# spi2par2019backpack.net
KiCad netlist of a schematic drawn in EAGLE
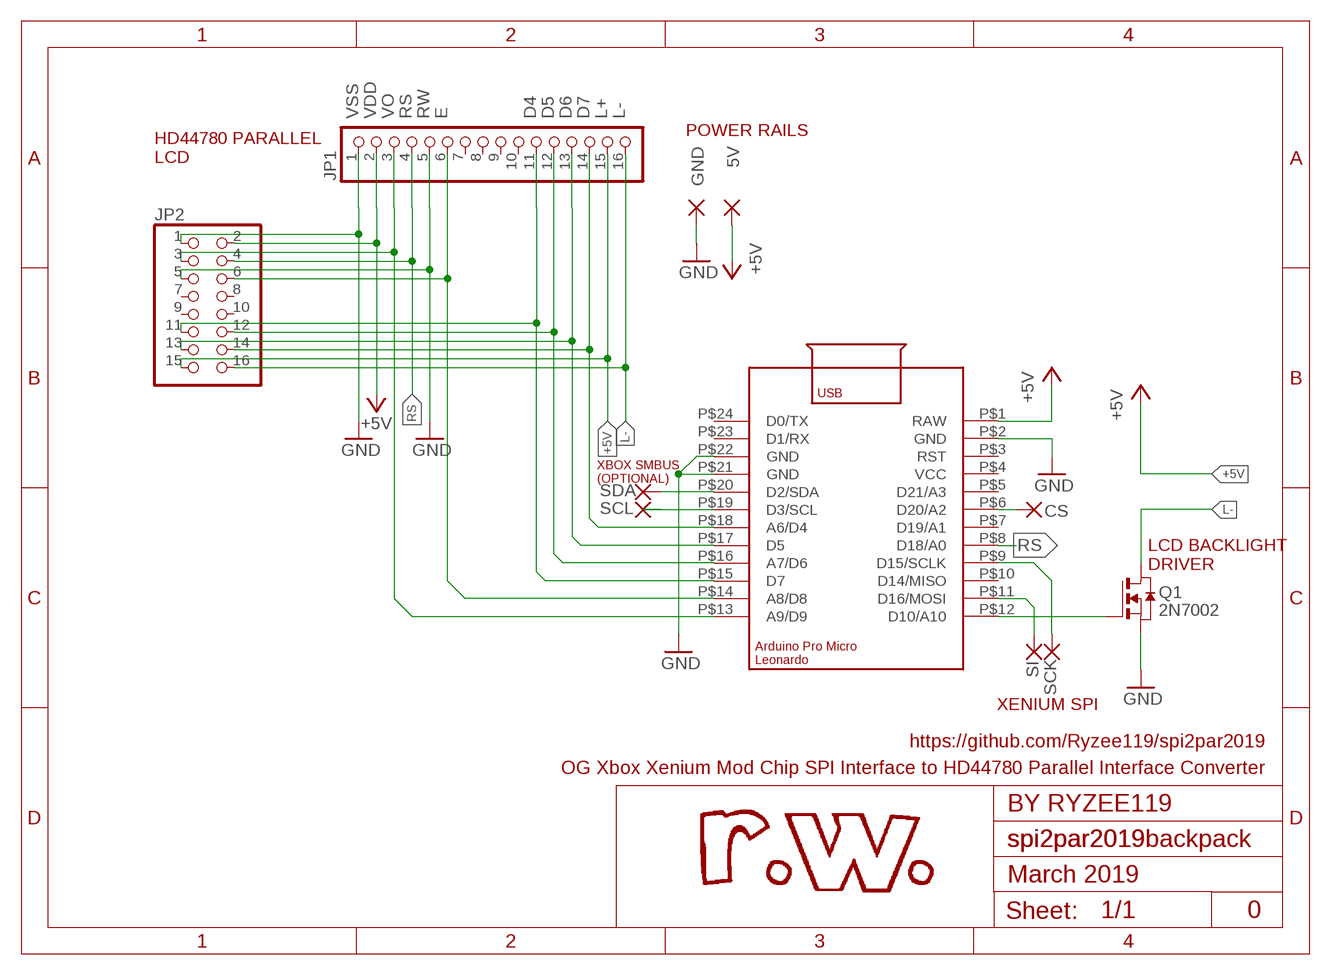
[diagram p0: schematic, sheet 1]

(export (version "E")
  (design (tool "Eeschema 10.0.6"))
  (components
    (comp (ref "5V")
      (value "WIREPADSMD1,27-254")
      (footprint "eagle-import:SMD1,27-2,54")
      (libsource (lib "eagle-import") (part "WIREPADSMD1,27-254"))
    )
    (comp (ref "CS")
      (value "WIREPADSMD1,27-254")
      (footprint "eagle-import:SMD1,27-2,54")
      (libsource (lib "eagle-import") (part "WIREPADSMD1,27-254"))
    )
    (comp (ref "GND")
      (value "WIREPADSMD1,27-254")
      (footprint "eagle-import:SMD1,27-2,54")
      (libsource (lib "eagle-import") (part "WIREPADSMD1,27-254"))
    )
    (comp (ref "JP1")
      (value "PINHD-1X16")
      (footprint "eagle-import:1X16")
      (libsource (lib "eagle-import") (part "PINHD-1X16"))
    )
    (comp (ref "JP2")
      (value "PINHD-2X8")
      (footprint "eagle-import:2X08")
      (libsource (lib "eagle-import") (part "PINHD-2X8"))
    )
    (comp (ref "Q1")
      (value "2N70026Ω")
      (footprint "eagle-import:SOT-23")
      (libsource (lib "eagle-import") (part "NMOSSOT23"))
    )
    (comp (ref "SCK")
      (value "WIREPADSMD1,27-254")
      (footprint "eagle-import:SMD1,27-2,54")
      (libsource (lib "eagle-import") (part "WIREPADSMD1,27-254"))
    )
    (comp (ref "SCL")
      (value "WIREPADSMD1,27-254")
      (footprint "eagle-import:SMD1,27-2,54")
      (libsource (lib "eagle-import") (part "WIREPADSMD1,27-254"))
    )
    (comp (ref "SDA")
      (value "WIREPADSMD1,27-254")
      (footprint "eagle-import:SMD1,27-2,54")
      (libsource (lib "eagle-import") (part "WIREPADSMD1,27-254"))
    )
    (comp (ref "SI")
      (value "WIREPADSMD1,27-254")
      (footprint "eagle-import:SMD1,27-2,54")
      (libsource (lib "eagle-import") (part "WIREPADSMD1,27-254"))
    )
    (comp (ref "U1")
      (value "ARDUINO_LEONARDO_MICRO")
      (footprint "eagle-import:ARDUINO_LEONARDO_MICRO")
      (libsource (lib "eagle-import") (part "ARDUINO_LEONARDO_MICRO"))
    )
  )
  (nets
    (net (code "1") (name "+5V") (class "Default")
      (node (ref "5V") (pin "1") (pinfunction "P_1") (pintype "passive"))
      (node (ref "JP1") (pin "15") (pinfunction "15_15") (pintype "passive"))
      (node (ref "JP1") (pin "2") (pinfunction "2_2") (pintype "passive"))
      (node (ref "JP2") (pin "15") (pinfunction "15_15") (pintype "passive"))
      (node (ref "JP2") (pin "2") (pinfunction "2_2") (pintype "passive"))
      (node (ref "U1") (pin "P$1") (pinfunction "RAW_P$1") (pintype "bidirectional"))
    )
    (net (code "2") (name "GND") (class "Default")
      (node (ref "GND") (pin "1") (pinfunction "P_1") (pintype "passive"))
      (node (ref "JP1") (pin "1") (pinfunction "1_1") (pintype "passive"))
      (node (ref "JP1") (pin "5") (pinfunction "5_5") (pintype "passive"))
      (node (ref "JP2") (pin "1") (pinfunction "1_1") (pintype "passive"))
      (node (ref "JP2") (pin "5") (pinfunction "5_5") (pintype "passive"))
      (node (ref "Q1") (pin "2") (pinfunction "S_2") (pintype "passive"))
      (node (ref "U1") (pin "P$2") (pinfunction "GND_P$2") (pintype "bidirectional"))
      (node (ref "U1") (pin "P$21") (pinfunction "GND_P$21") (pintype "bidirectional"))
      (node (ref "U1") (pin "P$22") (pinfunction "GND_P$22") (pintype "bidirectional"))
    )
    (net (code "3") (name "L-") (class "Default")
      (node (ref "JP1") (pin "16") (pinfunction "16_16") (pintype "passive"))
      (node (ref "JP2") (pin "16") (pinfunction "16_16") (pintype "passive"))
      (node (ref "Q1") (pin "1") (pinfunction "D_1") (pintype "passive"))
    )
    (net (code "4") (name "Net-(CS-P)") (class "Default")
      (node (ref "CS") (pin "1") (pinfunction "P_1") (pintype "passive"))
      (node (ref "U1") (pin "P$6") (pinfunction "D20/A2_P$6") (pintype "bidirectional"))
    )
    (net (code "5") (name "Net-(Q1-G)") (class "Default")
      (node (ref "Q1") (pin "3") (pinfunction "G_3") (pintype "passive"))
      (node (ref "U1") (pin "P$12") (pinfunction "D10/A10_P$12") (pintype "bidirectional"))
    )
    (net (code "6") (name "Net-(SCK-P)") (class "Default")
      (node (ref "SCK") (pin "1") (pinfunction "P_1") (pintype "passive"))
      (node (ref "U1") (pin "P$9") (pinfunction "D15/SCLK_P$9") (pintype "bidirectional"))
    )
    (net (code "7") (name "Net-(SCL-P)") (class "Default")
      (node (ref "SCL") (pin "1") (pinfunction "P_1") (pintype "passive"))
      (node (ref "U1") (pin "P$19") (pinfunction "D3/SCL_P$19") (pintype "bidirectional"))
    )
    (net (code "8") (name "Net-(SDA-P)") (class "Default")
      (node (ref "SDA") (pin "1") (pinfunction "P_1") (pintype "passive"))
      (node (ref "U1") (pin "P$20") (pinfunction "D2/SDA_P$20") (pintype "bidirectional"))
    )
    (net (code "9") (name "Net-(SI-P)") (class "Default")
      (node (ref "SI") (pin "1") (pinfunction "P_1") (pintype "passive"))
      (node (ref "U1") (pin "P$11") (pinfunction "D16/MOSI_P$11") (pintype "bidirectional"))
    )
    (net (code "10") (name "Net-(U1-A6{slash}D4)") (class "Default")
      (node (ref "JP1") (pin "14") (pinfunction "14_14") (pintype "passive"))
      (node (ref "JP2") (pin "14") (pinfunction "14_14") (pintype "passive"))
      (node (ref "U1") (pin "P$18") (pinfunction "A6/D4_P$18") (pintype "bidirectional"))
    )
    (net (code "11") (name "Net-(U1-A7{slash}D6)") (class "Default")
      (node (ref "JP1") (pin "12") (pinfunction "12_12") (pintype "passive"))
      (node (ref "JP2") (pin "12") (pinfunction "12_12") (pintype "passive"))
      (node (ref "U1") (pin "P$16") (pinfunction "A7/D6_P$16") (pintype "bidirectional"))
    )
    (net (code "12") (name "Net-(U1-A8{slash}D8)") (class "Default")
      (node (ref "JP1") (pin "6") (pinfunction "6_6") (pintype "passive"))
      (node (ref "JP2") (pin "6") (pinfunction "6_6") (pintype "passive"))
      (node (ref "U1") (pin "P$14") (pinfunction "A8/D8_P$14") (pintype "bidirectional"))
    )
    (net (code "13") (name "Net-(U1-A9{slash}D9)") (class "Default")
      (node (ref "JP1") (pin "3") (pinfunction "3_3") (pintype "passive"))
      (node (ref "JP2") (pin "3") (pinfunction "3_3") (pintype "passive"))
      (node (ref "U1") (pin "P$13") (pinfunction "A9/D9_P$13") (pintype "bidirectional"))
    )
    (net (code "14") (name "Net-(U1-D5)") (class "Default")
      (node (ref "JP1") (pin "13") (pinfunction "13_13") (pintype "passive"))
      (node (ref "JP2") (pin "13") (pinfunction "13_13") (pintype "passive"))
      (node (ref "U1") (pin "P$17") (pinfunction "D5_P$17") (pintype "bidirectional"))
    )
    (net (code "15") (name "Net-(U1-D7)") (class "Default")
      (node (ref "JP1") (pin "11") (pinfunction "11_11") (pintype "passive"))
      (node (ref "JP2") (pin "11") (pinfunction "11_11") (pintype "passive"))
      (node (ref "U1") (pin "P$15") (pinfunction "D7_P$15") (pintype "bidirectional"))
    )
    (net (code "16") (name "RS") (class "Default")
      (node (ref "JP1") (pin "4") (pinfunction "4_4") (pintype "passive"))
      (node (ref "JP2") (pin "4") (pinfunction "4_4") (pintype "passive"))
      (node (ref "U1") (pin "P$8") (pinfunction "D18/A0_P$8") (pintype "bidirectional"))
    )
    (net (code "17") (name "unconnected-(JP1-Pad7)") (class "Default")
      (node (ref "JP1") (pin "7") (pinfunction "7_7") (pintype "passive"))
    )
    (net (code "18") (name "unconnected-(JP1-Pad8)") (class "Default")
      (node (ref "JP1") (pin "8") (pinfunction "8_8") (pintype "passive"))
    )
    (net (code "19") (name "unconnected-(JP1-Pad9)") (class "Default")
      (node (ref "JP1") (pin "9") (pinfunction "9_9") (pintype "passive"))
    )
    (net (code "20") (name "unconnected-(JP1-Pad10)") (class "Default")
      (node (ref "JP1") (pin "10") (pinfunction "10_10") (pintype "passive"))
    )
    (net (code "21") (name "unconnected-(JP2-Pad7)") (class "Default")
      (node (ref "JP2") (pin "7") (pinfunction "7_7") (pintype "passive"))
    )
    (net (code "22") (name "unconnected-(JP2-Pad8)") (class "Default")
      (node (ref "JP2") (pin "8") (pinfunction "8_8") (pintype "passive"))
    )
    (net (code "23") (name "unconnected-(JP2-Pad9)") (class "Default")
      (node (ref "JP2") (pin "9") (pinfunction "9_9") (pintype "passive"))
    )
    (net (code "24") (name "unconnected-(JP2-Pad10)") (class "Default")
      (node (ref "JP2") (pin "10") (pinfunction "10_10") (pintype "passive"))
    )
    (net (code "25") (name "unconnected-(U1-D0{slash}TX-PadP$24)") (class "Default")
      (node (ref "U1") (pin "P$24") (pinfunction "D0/TX_P$24") (pintype "bidirectional"))
    )
    (net (code "26") (name "unconnected-(U1-D1{slash}RX-PadP$23)") (class "Default")
      (node (ref "U1") (pin "P$23") (pinfunction "D1/RX_P$23") (pintype "bidirectional"))
    )
    (net (code "27") (name "unconnected-(U1-D14{slash}MISO-PadP$10)") (class "Default")
      (node (ref "U1") (pin "P$10") (pinfunction "D14/MISO_P$10") (pintype "bidirectional"))
    )
    (net (code "28") (name "unconnected-(U1-D19{slash}A1-PadP$7)") (class "Default")
      (node (ref "U1") (pin "P$7") (pinfunction "D19/A1_P$7") (pintype "bidirectional"))
    )
    (net (code "29") (name "unconnected-(U1-D21{slash}A3-PadP$5)") (class "Default")
      (node (ref "U1") (pin "P$5") (pinfunction "D21/A3_P$5") (pintype "bidirectional"))
    )
    (net (code "30") (name "unconnected-(U1-RST-PadP$3)") (class "Default")
      (node (ref "U1") (pin "P$3") (pinfunction "RST_P$3") (pintype "bidirectional"))
    )
    (net (code "31") (name "unconnected-(U1-VCC-PadP$4)") (class "Default")
      (node (ref "U1") (pin "P$4") (pinfunction "VCC_P$4") (pintype "bidirectional"))
    )
  )
)
